# MOBHUINO.net
KiCad netlist of a schematic drawn in EAGLE
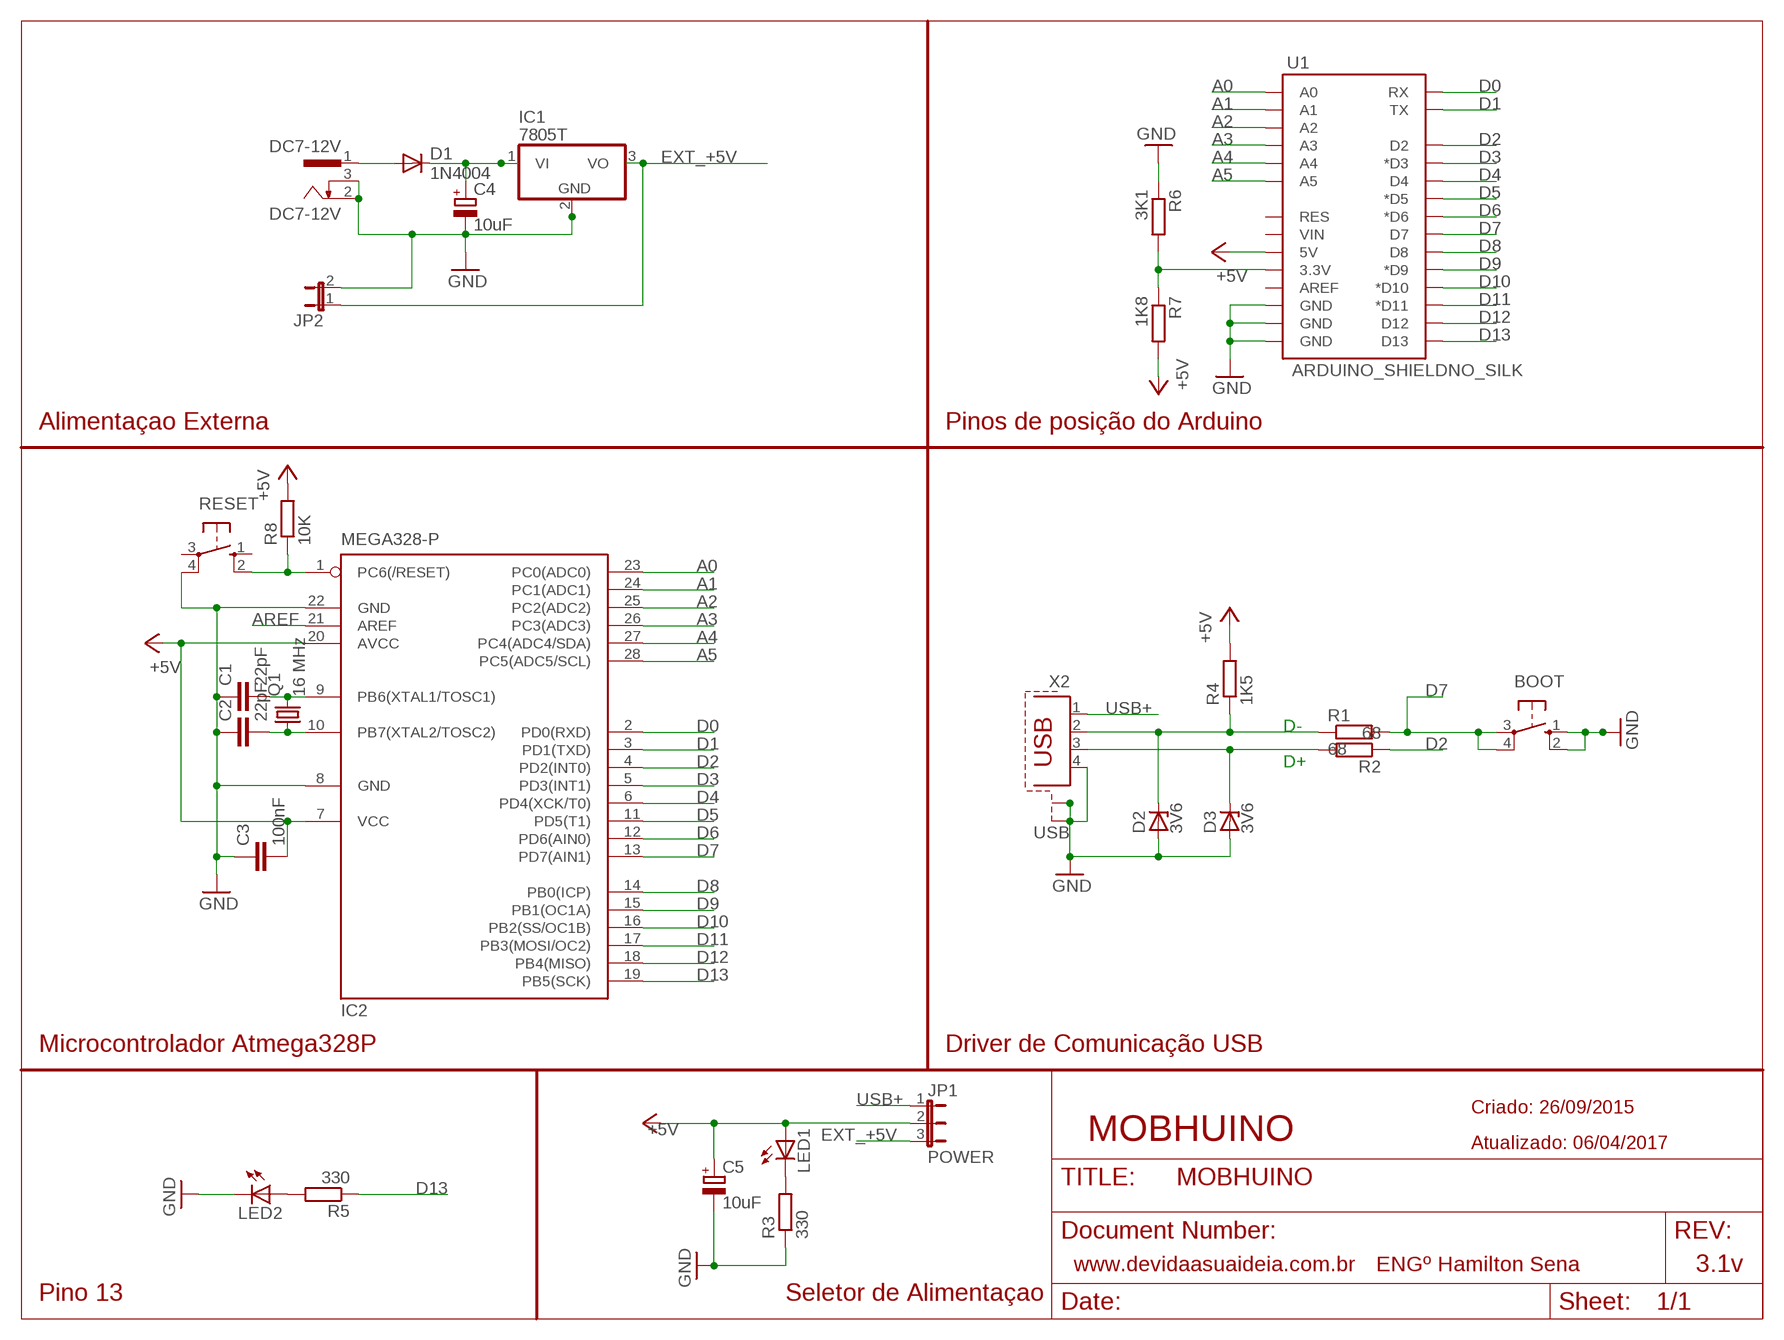
[diagram p0: schematic, sheet 1]

(export (version "E")
  (design (tool "Eeschema 10.0.6"))
  (components
    (comp (ref "BOOT")
      (value "10-XX")
      (footprint "eagle-import:B3F-10XX")
      (fields (field (name "MPN") "B3F-1000"))
      (libsource (lib "eagle-import") (part "10-XX"))
    )
    (comp (ref "C1")
      (value "22pF")
      (footprint "eagle-import:C025-024X044")
      (libsource (lib "eagle-import") (part "C-EU025-024X044"))
    )
    (comp (ref "C2")
      (value "22pF")
      (footprint "eagle-import:C025-024X044")
      (libsource (lib "eagle-import") (part "C-EU025-024X044"))
    )
    (comp (ref "C3")
      (value "100nF")
      (footprint "eagle-import:C050-024X044")
      (libsource (lib "eagle-import") (part "C-EU050-024X044"))
    )
    (comp (ref "C4")
      (value "10uF")
      (footprint "eagle-import:E2,5-6")
      (libsource (lib "eagle-import") (part "CPOL-EUE2.5-6"))
    )
    (comp (ref "C5")
      (value "10uF")
      (footprint "eagle-import:E2,5-6")
      (libsource (lib "eagle-import") (part "CPOL-EUE2.5-6"))
    )
    (comp (ref "D1")
      (value "1N4004")
      (footprint "eagle-import:DO41-10")
      (libsource (lib "eagle-import") (part "1N4004"))
    )
    (comp (ref "D2")
      (value "3V6")
      (footprint "eagle-import:DO34Z7")
      (libsource (lib "eagle-import") (part "ZENER-DIODEDO34-7"))
    )
    (comp (ref "D3")
      (value "3V6")
      (footprint "eagle-import:DO34Z7")
      (libsource (lib "eagle-import") (part "ZENER-DIODEDO34-7"))
    )
    (comp (ref "DC7-12V")
      (value "DC7-12V")
      (footprint "eagle-import:733980-62")
      (libsource (lib "eagle-import") (part "73398?0-62"))
    )
    (comp (ref "IC1")
      (value "7805T")
      (footprint "eagle-import:TO220H")
      (libsource (lib "eagle-import") (part "78T05"))
    )
    (comp (ref "IC2")
      (value "MEGA328-P")
      (footprint "eagle-import:DIL28-3")
      (libsource (lib "eagle-import") (part "MEGA8-P"))
    )
    (comp (ref "JP1")
      (value "POWER")
      (footprint "eagle-import:JP2")
      (libsource (lib "eagle-import") (part "JP2E"))
    )
    (comp (ref "JP2")
      (value "JP1E")
      (footprint "eagle-import:JP1")
      (libsource (lib "eagle-import") (part "JP1E"))
    )
    (comp (ref "LED1")
      (value "LED3MM")
      (footprint "eagle-import:LED3MM")
      (libsource (lib "eagle-import") (part "LED3MM"))
    )
    (comp (ref "LED2")
      (value "LED3MM")
      (footprint "eagle-import:LED3MM")
      (libsource (lib "eagle-import") (part "LED3MM"))
    )
    (comp (ref "Q1")
      (value "16 MHz")
      (footprint "eagle-import:HC49_S")
      (libsource (lib "eagle-import") (part "CRYSTALHC49S"))
    )
    (comp (ref "R1")
      (value "68")
      (footprint "eagle-import:0207_7")
      (libsource (lib "eagle-import") (part "R-EU_0207/7"))
    )
    (comp (ref "R2")
      (value "68")
      (footprint "eagle-import:0207_7")
      (libsource (lib "eagle-import") (part "R-EU_0207/7"))
    )
    (comp (ref "R3")
      (value "330")
      (footprint "eagle-import:0207_7")
      (libsource (lib "eagle-import") (part "R-EU_0207/7"))
    )
    (comp (ref "R4")
      (value "1K5")
      (footprint "eagle-import:0207_7")
      (libsource (lib "eagle-import") (part "R-EU_0207/7"))
    )
    (comp (ref "R5")
      (value "330")
      (footprint "eagle-import:0207_7")
      (libsource (lib "eagle-import") (part "R-EU_0207/7"))
    )
    (comp (ref "R6")
      (value "3K1")
      (footprint "eagle-import:0207_7")
      (libsource (lib "eagle-import") (part "R-EU_0207/7"))
    )
    (comp (ref "R7")
      (value "1K8")
      (footprint "eagle-import:0207_7")
      (libsource (lib "eagle-import") (part "R-EU_0207/7"))
    )
    (comp (ref "R8")
      (value "10K")
      (footprint "eagle-import:0207_7")
      (libsource (lib "eagle-import") (part "R-EU_0207/7"))
    )
    (comp (ref "RESET")
      (value "10-XX")
      (footprint "eagle-import:B3F-10XX")
      (fields (field (name "MPN") "B3F-1000"))
      (libsource (lib "eagle-import") (part "10-XX"))
    )
    (comp (ref "U1")
      (value "ARDUINO_SHIELDNO_SILK")
      (footprint "eagle-import:DUEMILANOVE_VIAS")
      (libsource (lib "eagle-import") (part "ARDUINO_SHIELDNO_SILK"))
    )
    (comp (ref "X2")
      (value "USB")
      (footprint "eagle-import:PN61729-S")
      (libsource (lib "eagle-import") (part "PN61729-S"))
    )
  )
  (nets
    (net (code "1") (name "+5V") (class "Default")
      (node (ref "C3") (pin "2") (pinfunction "2_2") (pintype "passive"))
      (node (ref "C5") (pin "+") (pinfunction "+_+") (pintype "passive"))
      (node (ref "IC2") (pin "20") (pinfunction "AVCC_20") (pintype "power_in"))
      (node (ref "IC2") (pin "7") (pinfunction "VCC_7") (pintype "power_in"))
      (node (ref "JP1") (pin "2") (pinfunction "2_2") (pintype "passive"))
      (node (ref "LED1") (pin "A") (pinfunction "A_A") (pintype "passive"))
      (node (ref "R4") (pin "2") (pinfunction "2_2") (pintype "passive"))
      (node (ref "R7") (pin "2") (pinfunction "2_2") (pintype "passive"))
      (node (ref "R8") (pin "2") (pinfunction "2_2") (pintype "passive"))
      (node (ref "U1") (pin "5V") (pinfunction "5V_5V") (pintype "bidirectional"))
    )
    (net (code "2") (name "/A0") (class "Default")
      (node (ref "IC2") (pin "23") (pinfunction "PC0(ADC0)_23") (pintype "bidirectional"))
      (node (ref "U1") (pin "A0") (pinfunction "A0_A0") (pintype "bidirectional"))
    )
    (net (code "3") (name "/A1") (class "Default")
      (node (ref "IC2") (pin "24") (pinfunction "PC1(ADC1)_24") (pintype "bidirectional"))
      (node (ref "U1") (pin "A1") (pinfunction "A1_A1") (pintype "bidirectional"))
    )
    (net (code "4") (name "/A2") (class "Default")
      (node (ref "IC2") (pin "25") (pinfunction "PC2(ADC2)_25") (pintype "bidirectional"))
      (node (ref "U1") (pin "A2") (pinfunction "A2_A2") (pintype "bidirectional"))
    )
    (net (code "5") (name "/A3") (class "Default")
      (node (ref "IC2") (pin "26") (pinfunction "PC3(ADC3)_26") (pintype "bidirectional"))
      (node (ref "U1") (pin "A3") (pinfunction "A3_A3") (pintype "bidirectional"))
    )
    (net (code "6") (name "/A4") (class "Default")
      (node (ref "IC2") (pin "27") (pinfunction "PC4(ADC4/SDA)_27") (pintype "bidirectional"))
      (node (ref "U1") (pin "A4") (pinfunction "A4_A4") (pintype "bidirectional"))
    )
    (net (code "7") (name "/A5") (class "Default")
      (node (ref "IC2") (pin "28") (pinfunction "PC5(ADC5/SCL)_28") (pintype "bidirectional"))
      (node (ref "U1") (pin "A5") (pinfunction "A5_A5") (pintype "bidirectional"))
    )
    (net (code "8") (name "/AREF") (class "Default")
      (node (ref "IC2") (pin "21") (pinfunction "AREF_21") (pintype "passive"))
    )
    (net (code "9") (name "/D0") (class "Default")
      (node (ref "IC2") (pin "2") (pinfunction "PD0(RXD)_2") (pintype "bidirectional"))
      (node (ref "U1") (pin "RX") (pinfunction "RX_RX") (pintype "bidirectional"))
    )
    (net (code "10") (name "/D1") (class "Default")
      (node (ref "IC2") (pin "3") (pinfunction "PD1(TXD)_3") (pintype "bidirectional"))
      (node (ref "U1") (pin "TX") (pinfunction "TX_TX") (pintype "bidirectional"))
    )
    (net (code "11") (name "/D2") (class "Default")
      (node (ref "IC2") (pin "4") (pinfunction "PD2(INT0)_4") (pintype "bidirectional"))
      (node (ref "R2") (pin "1") (pinfunction "1_1") (pintype "passive"))
      (node (ref "U1") (pin "D2") (pinfunction "D2_D2") (pintype "bidirectional"))
    )
    (net (code "12") (name "/D3") (class "Default")
      (node (ref "IC2") (pin "5") (pinfunction "PD3(INT1)_5") (pintype "bidirectional"))
      (node (ref "U1") (pin "D3") (pinfunction "*D3_D3") (pintype "bidirectional"))
    )
    (net (code "13") (name "/D4") (class "Default")
      (node (ref "IC2") (pin "6") (pinfunction "PD4(XCK/T0)_6") (pintype "bidirectional"))
      (node (ref "U1") (pin "D4") (pinfunction "D4_D4") (pintype "bidirectional"))
    )
    (net (code "14") (name "/D5") (class "Default")
      (node (ref "IC2") (pin "11") (pinfunction "PD5(T1)_11") (pintype "bidirectional"))
      (node (ref "U1") (pin "D5") (pinfunction "*D5_D5") (pintype "bidirectional"))
    )
    (net (code "15") (name "/D6") (class "Default")
      (node (ref "IC2") (pin "12") (pinfunction "PD6(AIN0)_12") (pintype "bidirectional"))
      (node (ref "U1") (pin "D6") (pinfunction "*D6_D6") (pintype "bidirectional"))
    )
    (net (code "16") (name "/D7") (class "Default")
      (node (ref "BOOT") (pin "3") (pinfunction "P_3") (pintype "passive"))
      (node (ref "BOOT") (pin "4") (pinfunction "P1_4") (pintype "passive"))
      (node (ref "IC2") (pin "13") (pinfunction "PD7(AIN1)_13") (pintype "bidirectional"))
      (node (ref "R1") (pin "2") (pinfunction "2_2") (pintype "passive"))
      (node (ref "U1") (pin "D7") (pinfunction "D7_D7") (pintype "bidirectional"))
    )
    (net (code "17") (name "/D8") (class "Default")
      (node (ref "IC2") (pin "14") (pinfunction "PB0(ICP)_14") (pintype "bidirectional"))
      (node (ref "U1") (pin "D8") (pinfunction "D8_D8") (pintype "bidirectional"))
    )
    (net (code "18") (name "/D9") (class "Default")
      (node (ref "IC2") (pin "15") (pinfunction "PB1(OC1A)_15") (pintype "bidirectional"))
      (node (ref "U1") (pin "D9") (pinfunction "*D9_D9") (pintype "bidirectional"))
    )
    (net (code "19") (name "/D10") (class "Default")
      (node (ref "IC2") (pin "16") (pinfunction "PB2(SS/OC1B)_16") (pintype "bidirectional"))
      (node (ref "U1") (pin "D10") (pinfunction "*D10_D10") (pintype "bidirectional"))
    )
    (net (code "20") (name "/D11") (class "Default")
      (node (ref "IC2") (pin "17") (pinfunction "PB3(MOSI/OC2)_17") (pintype "bidirectional"))
      (node (ref "U1") (pin "D11") (pinfunction "*D11_D11") (pintype "bidirectional"))
    )
    (net (code "21") (name "/D12") (class "Default")
      (node (ref "IC2") (pin "18") (pinfunction "PB4(MISO)_18") (pintype "bidirectional"))
      (node (ref "U1") (pin "D12") (pinfunction "D12_D12") (pintype "bidirectional"))
    )
    (net (code "22") (name "/D13") (class "Default")
      (node (ref "IC2") (pin "19") (pinfunction "PB5(SCK)_19") (pintype "bidirectional"))
      (node (ref "R5") (pin "1") (pinfunction "1_1") (pintype "passive"))
      (node (ref "U1") (pin "D13") (pinfunction "D13_D13") (pintype "bidirectional"))
    )
    (net (code "23") (name "/EXT_+5V") (class "Default")
      (node (ref "IC1") (pin "3") (pinfunction "VO_3") (pintype "passive"))
      (node (ref "JP1") (pin "3") (pinfunction "3_3") (pintype "passive"))
      (node (ref "JP2") (pin "1") (pinfunction "1_1") (pintype "passive"))
    )
    (net (code "24") (name "/USB+") (class "Default")
      (node (ref "JP1") (pin "1") (pinfunction "1_1") (pintype "passive"))
      (node (ref "X2") (pin "1") (pinfunction "1_1") (pintype "passive"))
    )
    (net (code "25") (name "GND") (class "Default")
      (node (ref "BOOT") (pin "1") (pinfunction "S_1") (pintype "passive"))
      (node (ref "BOOT") (pin "2") (pinfunction "S1_2") (pintype "passive"))
      (node (ref "C1") (pin "1") (pinfunction "1_1") (pintype "passive"))
      (node (ref "C2") (pin "1") (pinfunction "1_1") (pintype "passive"))
      (node (ref "C3") (pin "1") (pinfunction "1_1") (pintype "passive"))
      (node (ref "C4") (pin "-") (pinfunction "-_-") (pintype "passive"))
      (node (ref "C5") (pin "-") (pinfunction "-_-") (pintype "passive"))
      (node (ref "D2") (pin "A") (pinfunction "A_A") (pintype "passive"))
      (node (ref "D3") (pin "A") (pinfunction "A_A") (pintype "passive"))
      (node (ref "DC7-12V") (pin "2") (pinfunction "2_2") (pintype "passive"))
      (node (ref "DC7-12V") (pin "3") (pinfunction "3_3") (pintype "passive"))
      (node (ref "IC1") (pin "2") (pinfunction "GND_2") (pintype "passive"))
      (node (ref "IC2") (pin "22") (pinfunction "GND_22") (pintype "power_in"))
      (node (ref "IC2") (pin "8") (pinfunction "GND_8") (pintype "power_in"))
      (node (ref "JP2") (pin "2") (pinfunction "2_2") (pintype "passive"))
      (node (ref "LED2") (pin "K") (pinfunction "C_K") (pintype "passive"))
      (node (ref "R3") (pin "1") (pinfunction "1_1") (pintype "passive"))
      (node (ref "R6") (pin "1") (pinfunction "1_1") (pintype "passive"))
      (node (ref "RESET") (pin "4") (pinfunction "P1_4") (pintype "passive"))
      (node (ref "U1") (pin "GND@0") (pinfunction "GND_GND@0") (pintype "bidirectional"))
      (node (ref "U1") (pin "GND@1") (pinfunction "GND_GND@1") (pintype "bidirectional"))
      (node (ref "U1") (pin "GND@2") (pinfunction "GND_GND@2") (pintype "bidirectional"))
      (node (ref "X2") (pin "4") (pinfunction "4_4") (pintype "passive"))
      (node (ref "X2") (pin "S1") (pinfunction "S1_S1") (pintype "passive"))
      (node (ref "X2") (pin "S2") (pinfunction "S2_S2") (pintype "passive"))
    )
    (net (code "26") (name "Net-(D1-PadA)") (class "Default")
      (node (ref "D1") (pin "A") (pinfunction "A_A") (pintype "passive"))
      (node (ref "DC7-12V") (pin "1") (pinfunction "1_1") (pintype "passive"))
    )
    (net (code "27") (name "Net-(D2-PadC)") (class "Default")
      (node (ref "D2") (pin "C") (pinfunction "C_C") (pintype "passive"))
      (node (ref "R1") (pin "1") (pinfunction "1_1") (pintype "passive"))
      (node (ref "R4") (pin "1") (pinfunction "1_1") (pintype "passive"))
      (node (ref "X2") (pin "2") (pinfunction "2_2") (pintype "passive"))
    )
    (net (code "28") (name "Net-(D3-PadC)") (class "Default")
      (node (ref "D3") (pin "C") (pinfunction "C_C") (pintype "passive"))
      (node (ref "R2") (pin "2") (pinfunction "2_2") (pintype "passive"))
      (node (ref "X2") (pin "3") (pinfunction "3_3") (pintype "passive"))
    )
    (net (code "29") (name "Net-(IC1-VI)") (class "Default")
      (node (ref "C4") (pin "+") (pinfunction "+_+") (pintype "passive"))
      (node (ref "D1") (pin "C") (pinfunction "C_C") (pintype "passive"))
      (node (ref "IC1") (pin "1") (pinfunction "VI_1") (pintype "input"))
    )
    (net (code "30") (name "Net-(IC2-PB6(XTAL1{slash}TOSC1))") (class "Default")
      (node (ref "C1") (pin "2") (pinfunction "2_2") (pintype "passive"))
      (node (ref "IC2") (pin "9") (pinfunction "PB6(XTAL1/TOSC1)_9") (pintype "bidirectional"))
      (node (ref "Q1") (pin "2") (pinfunction "2_2") (pintype "passive"))
    )
    (net (code "31") (name "Net-(IC2-PB7(XTAL2{slash}TOSC2))") (class "Default")
      (node (ref "C2") (pin "2") (pinfunction "2_2") (pintype "passive"))
      (node (ref "IC2") (pin "10") (pinfunction "PB7(XTAL2/TOSC2)_10") (pintype "bidirectional"))
      (node (ref "Q1") (pin "1") (pinfunction "1_1") (pintype "passive"))
    )
    (net (code "32") (name "Net-(IC2-PC6({slash}RESET))") (class "Default")
      (node (ref "IC2") (pin "1") (pinfunction "PC6(/RESET)_1") (pintype "bidirectional"))
      (node (ref "R8") (pin "1") (pinfunction "1_1") (pintype "passive"))
      (node (ref "RESET") (pin "2") (pinfunction "S1_2") (pintype "passive"))
    )
    (net (code "33") (name "Net-(LED1-C)") (class "Default")
      (node (ref "LED1") (pin "K") (pinfunction "C_K") (pintype "passive"))
      (node (ref "R3") (pin "2") (pinfunction "2_2") (pintype "passive"))
    )
    (net (code "34") (name "Net-(LED2-PadA)") (class "Default")
      (node (ref "LED2") (pin "A") (pinfunction "A_A") (pintype "passive"))
      (node (ref "R5") (pin "2") (pinfunction "2_2") (pintype "passive"))
    )
    (net (code "35") (name "Net-(R6-Pad2)") (class "Default")
      (node (ref "R6") (pin "2") (pinfunction "2_2") (pintype "passive"))
      (node (ref "R7") (pin "1") (pinfunction "1_1") (pintype "passive"))
      (node (ref "U1") (pin "3.3V") (pinfunction "3.3V_3.3V") (pintype "bidirectional"))
    )
    (net (code "36") (name "unconnected-(RESET-P-Pad3)") (class "Default")
      (node (ref "RESET") (pin "3") (pinfunction "P_3") (pintype "passive"))
    )
    (net (code "37") (name "unconnected-(RESET-S-Pad1)") (class "Default")
      (node (ref "RESET") (pin "1") (pinfunction "S_1") (pintype "passive"))
    )
    (net (code "38") (name "unconnected-(U1-PadAREF)") (class "Default")
      (node (ref "U1") (pin "AREF") (pinfunction "AREF_AREF") (pintype "bidirectional"))
    )
    (net (code "39") (name "unconnected-(U1-PadRES)") (class "Default")
      (node (ref "U1") (pin "RES") (pinfunction "RES_RES") (pintype "bidirectional"))
    )
    (net (code "40") (name "unconnected-(U1-PadVIN)") (class "Default")
      (node (ref "U1") (pin "VIN") (pinfunction "VIN_VIN") (pintype "bidirectional"))
    )
  )
)
